# tricorder-sensor-apds9250-mk-1_0.net
KiCad netlist of a schematic drawn in EAGLE
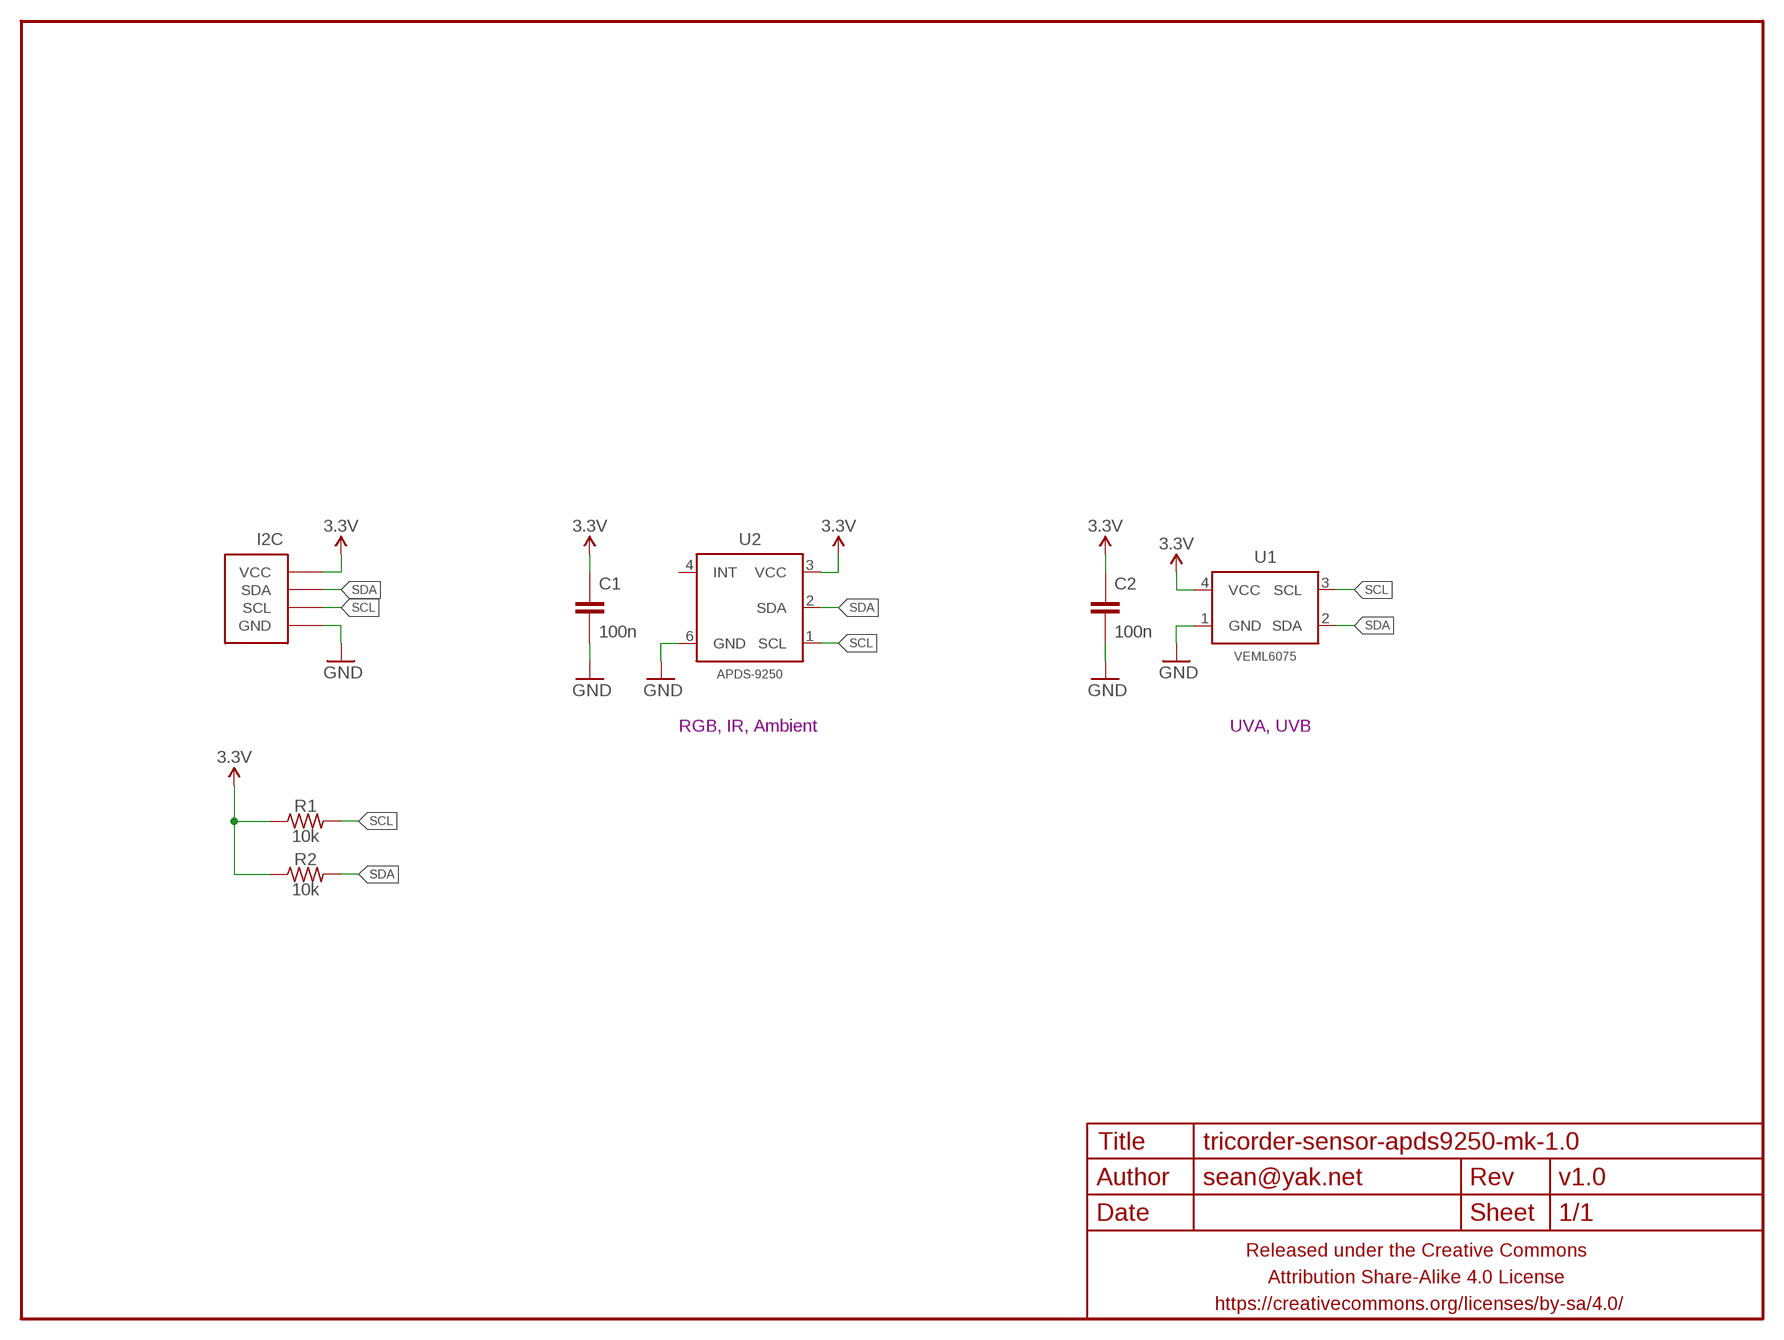
[diagram p0: schematic, sheet 1]

(export (version "E")
  (design (tool "Eeschema 10.0.6"))
  (components
    (comp (ref "C1")
      (value "100n")
      (footprint "eagle-import:C0603")
      (libsource (lib "eagle-import") (part "CAPACITOR-CERAMICC0603"))
    )
    (comp (ref "C2")
      (value "100n")
      (footprint "eagle-import:C0603")
      (libsource (lib "eagle-import") (part "CAPACITOR-CERAMICC0603"))
    )
    (comp (ref "FRAME1")
      (value "FRAME-LETTERNO_PACKAGE")
      (footprint "eagle-import:DUMMY")
      (fields (field (name "DESIGNER") "sean@yak.net") (field (name "VERSION") "v1.0"))
      (libsource (lib "eagle-import") (part "FRAME-LETTERNO_PACKAGE"))
    )
    (comp (ref "I2C")
      (value "M04-I2CPTH-0.1IN-CENTERED")
      (footprint "eagle-import:1X04-PTH-VERT-I2C-CENTERED")
      (libsource (lib "eagle-import") (part "M04-I2CPTH-0.1IN-CENTERED"))
    )
    (comp (ref "R1")
      (value "10k")
      (footprint "eagle-import:R0603")
      (libsource (lib "eagle-import") (part "RESISTORR0603"))
    )
    (comp (ref "R2")
      (value "10k")
      (footprint "eagle-import:R0603")
      (libsource (lib "eagle-import") (part "RESISTORR0603"))
    )
    (comp (ref "U1")
      (value "VEML6075")
      (footprint "eagle-import:OPLGA4")
      (libsource (lib "eagle-import") (part "VEML6075"))
    )
    (comp (ref "U2")
      (value "APDS-9250")
      (footprint "eagle-import:APDS-9250-ALT")
      (libsource (lib "eagle-import") (part "APDS-9250ALT"))
    )
  )
  (nets
    (net (code "1") (name "3.3V") (class "Default")
      (node (ref "C1") (pin "1") (pinfunction "1_1") (pintype "passive"))
      (node (ref "C2") (pin "1") (pinfunction "1_1") (pintype "passive"))
      (node (ref "I2C") (pin "VCC") (pinfunction "VCC_VCC") (pintype "bidirectional"))
      (node (ref "R1") (pin "1") (pinfunction "1_1") (pintype "passive"))
      (node (ref "R2") (pin "1") (pinfunction "1_1") (pintype "passive"))
      (node (ref "U1") (pin "4") (pinfunction "VCC_4") (pintype "bidirectional"))
      (node (ref "U2") (pin "3") (pinfunction "VCC_3") (pintype "bidirectional"))
    )
    (net (code "2") (name "GND") (class "Default")
      (node (ref "C1") (pin "2") (pinfunction "2_2") (pintype "passive"))
      (node (ref "C2") (pin "2") (pinfunction "2_2") (pintype "passive"))
      (node (ref "I2C") (pin "GND") (pinfunction "GND_GND") (pintype "bidirectional"))
      (node (ref "U1") (pin "1") (pinfunction "GND_1") (pintype "bidirectional"))
      (node (ref "U2") (pin "6") (pinfunction "GND_6") (pintype "bidirectional"))
    )
    (net (code "3") (name "SCL") (class "Default")
      (node (ref "I2C") (pin "SCL") (pinfunction "SCL_SCL") (pintype "bidirectional"))
      (node (ref "R1") (pin "2") (pinfunction "2_2") (pintype "passive"))
      (node (ref "U1") (pin "3") (pinfunction "SCL_3") (pintype "bidirectional"))
      (node (ref "U2") (pin "1") (pinfunction "SCL_1") (pintype "bidirectional"))
    )
    (net (code "4") (name "SDA") (class "Default")
      (node (ref "I2C") (pin "SDA") (pinfunction "SDA_SDA") (pintype "bidirectional"))
      (node (ref "R2") (pin "2") (pinfunction "2_2") (pintype "passive"))
      (node (ref "U1") (pin "2") (pinfunction "SDA_2") (pintype "bidirectional"))
      (node (ref "U2") (pin "2") (pinfunction "SDA_2") (pintype "bidirectional"))
    )
    (net (code "5") (name "unconnected-(U2-INT-Pad4)") (class "Default")
      (node (ref "U2") (pin "4") (pinfunction "INT_4") (pintype "bidirectional"))
    )
  )
)
